# Hypex_PSU_v6.net
KiCad netlist of a schematic drawn in EAGLE
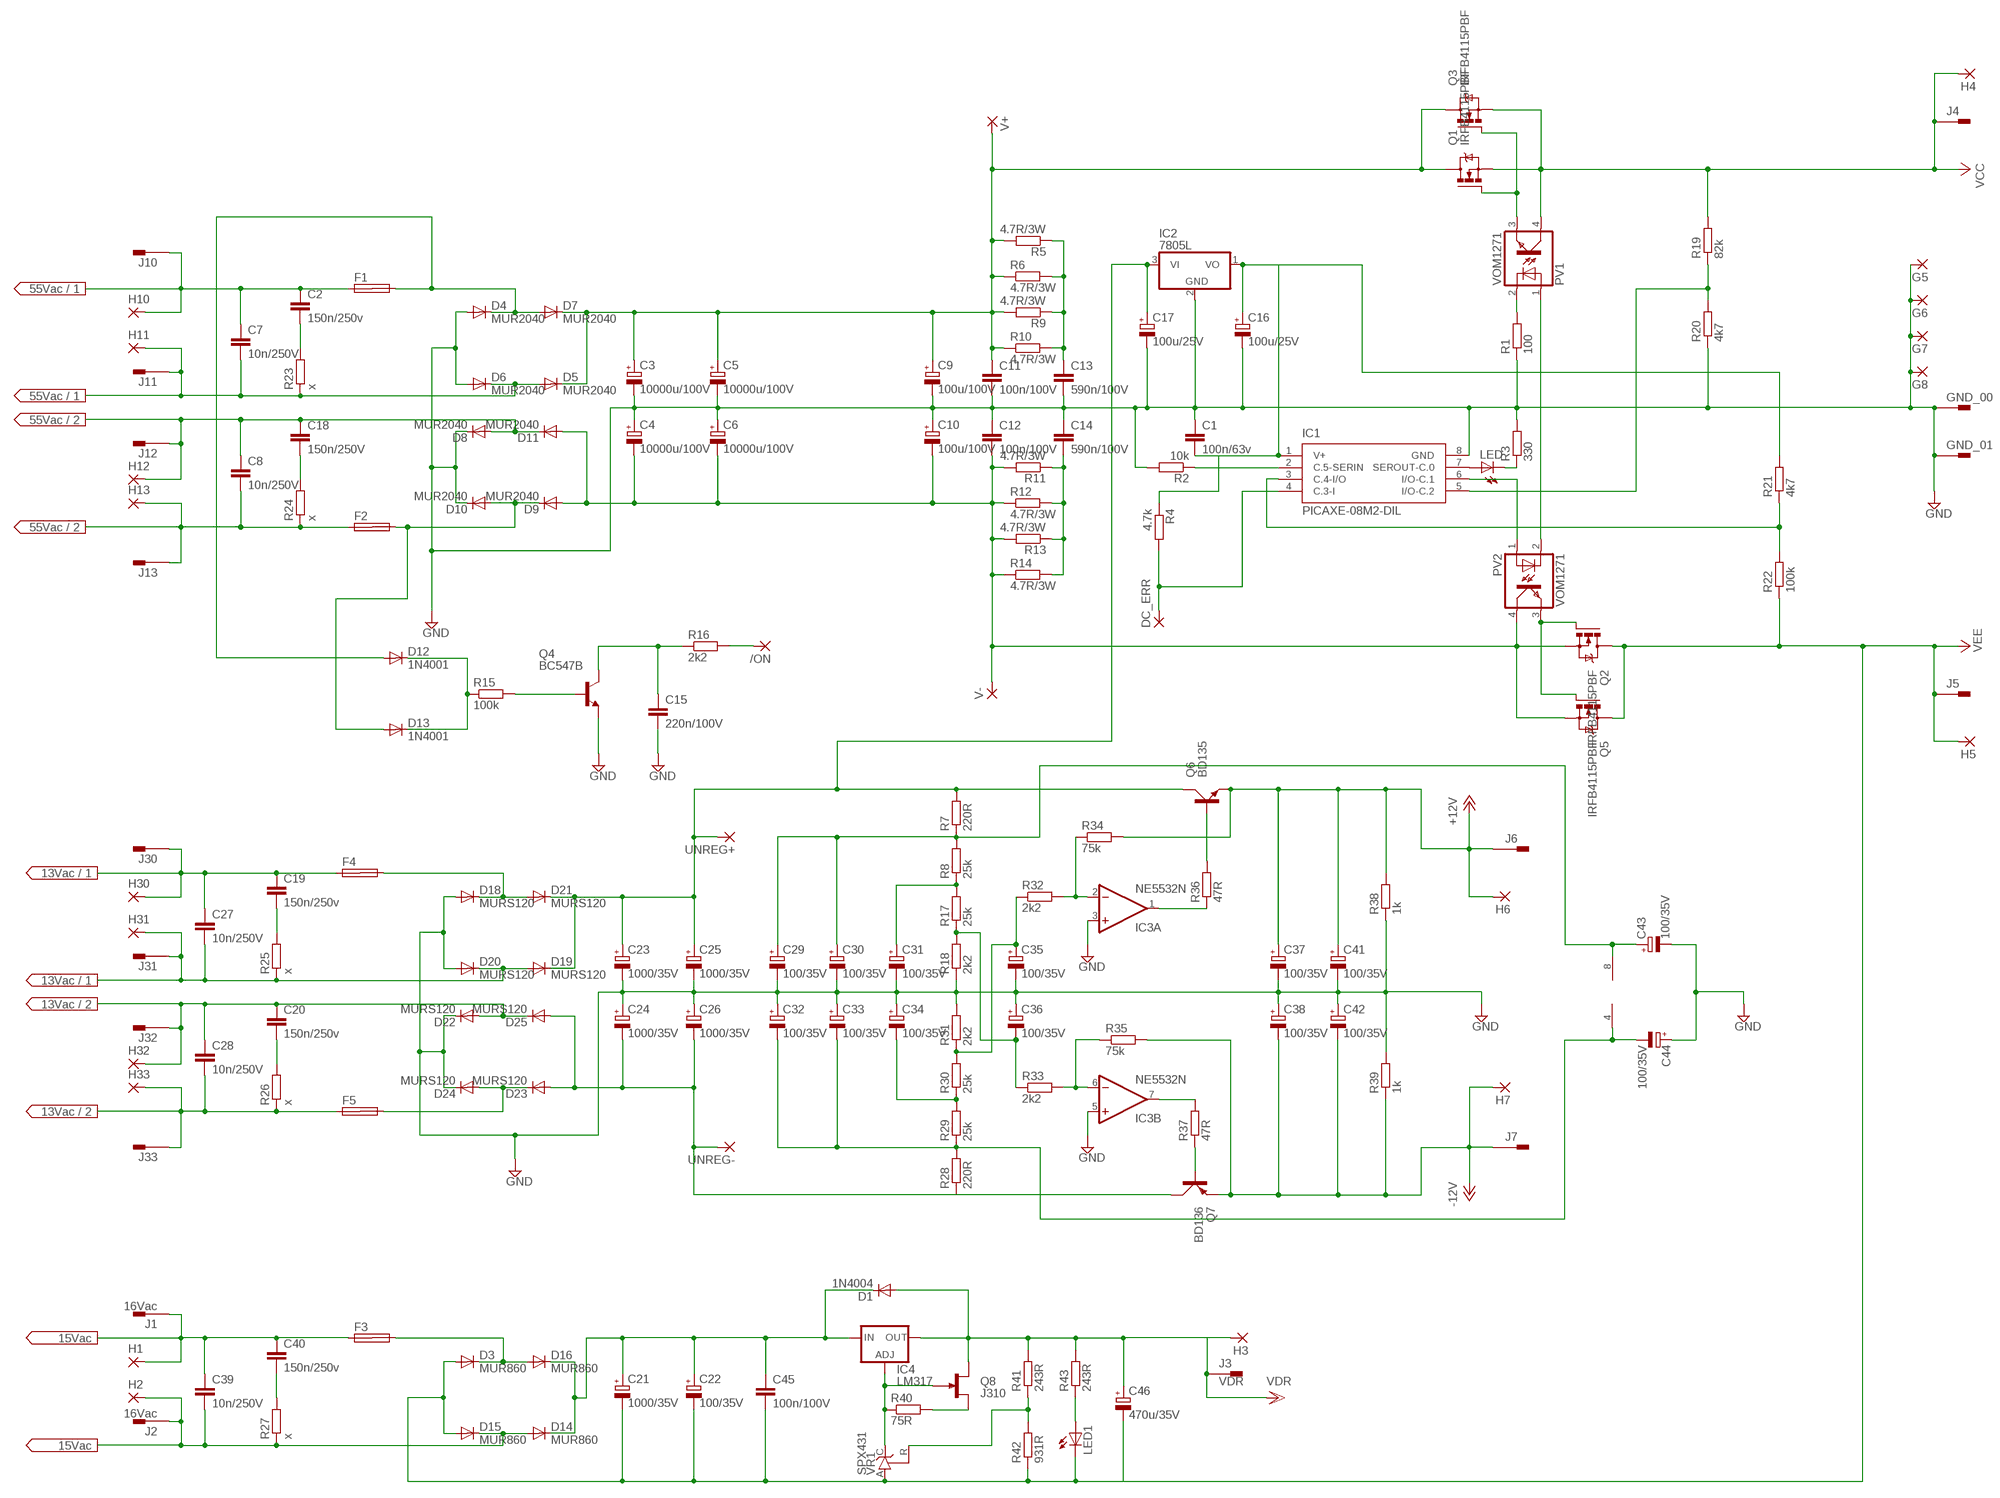
[diagram p0: schematic, sheet 1]

(export (version "E")
  (design (tool "Eeschema 10.0.6"))
  (components
    (comp (ref "/ON")
      (value "2,54/0,8")
      (footprint "eagle-import:2,54_0,8")
      (libsource (lib "eagle-import") (part "2,54/0,8"))
    )
    (comp (ref "C1")
      (value "100n/63v")
      (footprint "eagle-import:C050-025X075")
      (libsource (lib "eagle-import") (part "C-EU050-025X075"))
    )
    (comp (ref "C2")
      (value "150n/250v")
      (footprint "eagle-import:C102-064X133")
      (libsource (lib "eagle-import") (part "resistor_C-EU102-064X133"))
    )
    (comp (ref "C3")
      (value "10000u/100V")
      (footprint "eagle-import:EB35D")
      (libsource (lib "eagle-import") (part "CPOL-EUE10-35"))
    )
    (comp (ref "C4")
      (value "10000u/100V")
      (footprint "eagle-import:EB35D")
      (libsource (lib "eagle-import") (part "CPOL-EUE10-35"))
    )
    (comp (ref "C5")
      (value "10000u/100V")
      (footprint "eagle-import:EB35D")
      (libsource (lib "eagle-import") (part "CPOL-EUE10-35"))
    )
    (comp (ref "C6")
      (value "10000u/100V")
      (footprint "eagle-import:EB35D")
      (libsource (lib "eagle-import") (part "CPOL-EUE10-35"))
    )
    (comp (ref "C7")
      (value "10n/250V")
      (footprint "eagle-import:C102-064X133")
      (libsource (lib "eagle-import") (part "resistor_C-EU102-064X133"))
    )
    (comp (ref "C8")
      (value "10n/250V")
      (footprint "eagle-import:C102-064X133")
      (libsource (lib "eagle-import") (part "resistor_C-EU102-064X133"))
    )
    (comp (ref "C9")
      (value "100u/100V")
      (footprint "eagle-import:E5-10,5")
      (libsource (lib "eagle-import") (part "CPOL-EUE5-10.5"))
    )
    (comp (ref "C10")
      (value "100u/100V")
      (footprint "eagle-import:E5-10,5")
      (libsource (lib "eagle-import") (part "CPOL-EUE5-10.5"))
    )
    (comp (ref "C11")
      (value "100n/100V")
      (footprint "eagle-import:C102-064X133")
      (libsource (lib "eagle-import") (part "resistor_C-EU102-064X133"))
    )
    (comp (ref "C12")
      (value "100n/100V")
      (footprint "eagle-import:C102-064X133")
      (libsource (lib "eagle-import") (part "resistor_C-EU102-064X133"))
    )
    (comp (ref "C13")
      (value "590n/100V")
      (footprint "eagle-import:C102-064X133")
      (libsource (lib "eagle-import") (part "resistor_C-EU102-064X133"))
    )
    (comp (ref "C14")
      (value "590n/100V")
      (footprint "eagle-import:C102-064X133")
      (libsource (lib "eagle-import") (part "resistor_C-EU102-064X133"))
    )
    (comp (ref "C15")
      (value "220n/100V")
      (footprint "eagle-import:C102-064X133")
      (libsource (lib "eagle-import") (part "resistor_C-EU102-064X133"))
    )
    (comp (ref "C16")
      (value "100u/25V")
      (footprint "eagle-import:E3,5-8")
      (libsource (lib "eagle-import") (part "CPOL-EUE3.5-8"))
    )
    (comp (ref "C17")
      (value "100u/25V")
      (footprint "eagle-import:E3,5-8")
      (libsource (lib "eagle-import") (part "CPOL-EUE3.5-8"))
    )
    (comp (ref "C18")
      (value "150n/250V")
      (footprint "eagle-import:C102-064X133")
      (libsource (lib "eagle-import") (part "resistor_C-EU102-064X133"))
    )
    (comp (ref "C19")
      (value "150n/250v")
      (footprint "eagle-import:C102-064X133")
      (libsource (lib "eagle-import") (part "resistor_C-EU102-064X133"))
    )
    (comp (ref "C20")
      (value "150n/250v")
      (footprint "eagle-import:C102-064X133")
      (libsource (lib "eagle-import") (part "resistor_C-EU102-064X133"))
    )
    (comp (ref "C21")
      (value "1000/35V")
      (footprint "eagle-import:E5-13")
      (libsource (lib "eagle-import") (part "CPOL-EUE5-13"))
    )
    (comp (ref "C22")
      (value "100/35V")
      (footprint "eagle-import:E5-8,5")
      (libsource (lib "eagle-import") (part "CPOL-EUE5-8.5"))
    )
    (comp (ref "C23")
      (value "1000/35V")
      (footprint "eagle-import:E5-13")
      (libsource (lib "eagle-import") (part "CPOL-EUE5-13"))
    )
    (comp (ref "C24")
      (value "1000/35V")
      (footprint "eagle-import:E5-13")
      (libsource (lib "eagle-import") (part "CPOL-EUE5-13"))
    )
    (comp (ref "C25")
      (value "1000/35V")
      (footprint "eagle-import:E5-13")
      (libsource (lib "eagle-import") (part "CPOL-EUE5-13"))
    )
    (comp (ref "C26")
      (value "1000/35V")
      (footprint "eagle-import:E5-13")
      (libsource (lib "eagle-import") (part "CPOL-EUE5-13"))
    )
    (comp (ref "C27")
      (value "10n/250V")
      (footprint "eagle-import:C102-064X133")
      (libsource (lib "eagle-import") (part "resistor_C-EU102-064X133"))
    )
    (comp (ref "C28")
      (value "10n/250V")
      (footprint "eagle-import:C102-064X133")
      (libsource (lib "eagle-import") (part "resistor_C-EU102-064X133"))
    )
    (comp (ref "C29")
      (value "100/35V")
      (footprint "eagle-import:E5-8,5")
      (libsource (lib "eagle-import") (part "CPOL-EUE5-8.5"))
    )
    (comp (ref "C30")
      (value "100/35V")
      (footprint "eagle-import:E5-8,5")
      (libsource (lib "eagle-import") (part "CPOL-EUE5-8.5"))
    )
    (comp (ref "C31")
      (value "100/35V")
      (footprint "eagle-import:E5-8,5")
      (libsource (lib "eagle-import") (part "CPOL-EUE5-8.5"))
    )
    (comp (ref "C32")
      (value "100/35V")
      (footprint "eagle-import:E5-8,5")
      (libsource (lib "eagle-import") (part "CPOL-EUE5-8.5"))
    )
    (comp (ref "C33")
      (value "100/35V")
      (footprint "eagle-import:E5-8,5")
      (libsource (lib "eagle-import") (part "CPOL-EUE5-8.5"))
    )
    (comp (ref "C34")
      (value "100/35V")
      (footprint "eagle-import:E5-8,5")
      (libsource (lib "eagle-import") (part "CPOL-EUE5-8.5"))
    )
    (comp (ref "C35")
      (value "100/35V")
      (footprint "eagle-import:E5-8,5")
      (libsource (lib "eagle-import") (part "CPOL-EUE5-8.5"))
    )
    (comp (ref "C36")
      (value "100/35V")
      (footprint "eagle-import:E5-8,5")
      (libsource (lib "eagle-import") (part "CPOL-EUE5-8.5"))
    )
    (comp (ref "C37")
      (value "100/35V")
      (footprint "eagle-import:E5-8,5")
      (libsource (lib "eagle-import") (part "CPOL-EUE5-8.5"))
    )
    (comp (ref "C38")
      (value "100/35V")
      (footprint "eagle-import:E5-8,5")
      (libsource (lib "eagle-import") (part "CPOL-EUE5-8.5"))
    )
    (comp (ref "C39")
      (value "10n/250V")
      (footprint "eagle-import:C102-064X133")
      (libsource (lib "eagle-import") (part "resistor_C-EU102-064X133"))
    )
    (comp (ref "C40")
      (value "150n/250v")
      (footprint "eagle-import:C102-064X133")
      (libsource (lib "eagle-import") (part "resistor_C-EU102-064X133"))
    )
    (comp (ref "C41")
      (value "100/35V")
      (footprint "eagle-import:E5-8,5")
      (libsource (lib "eagle-import") (part "CPOL-EUE5-8.5"))
    )
    (comp (ref "C42")
      (value "100/35V")
      (footprint "eagle-import:E5-8,5")
      (libsource (lib "eagle-import") (part "CPOL-EUE5-8.5"))
    )
    (comp (ref "C43")
      (value "100/35V")
      (footprint "eagle-import:E5-8,5")
      (libsource (lib "eagle-import") (part "CPOL-EUE5-8.5"))
    )
    (comp (ref "C44")
      (value "100/35V")
      (footprint "eagle-import:E5-8,5")
      (libsource (lib "eagle-import") (part "CPOL-EUE5-8.5"))
    )
    (comp (ref "C45")
      (value "100n/100V")
      (footprint "eagle-import:C102-064X133")
      (libsource (lib "eagle-import") (part "resistor_C-EU102-064X133"))
    )
    (comp (ref "C46")
      (value "470u/35V")
      (footprint "eagle-import:E5-8,5")
      (libsource (lib "eagle-import") (part "CPOL-EUE5-8.5"))
    )
    (comp (ref "D1")
      (value "1N4004")
      (footprint "eagle-import:DO41-10")
      (libsource (lib "eagle-import") (part "1N4004"))
    )
    (comp (ref "D3")
      (value "MUR860")
      (footprint "eagle-import:TO220ACS")
      (libsource (lib "eagle-import") (part "MUR810"))
    )
    (comp (ref "D4")
      (value "MUR2040")
      (footprint "eagle-import:TO220ACS")
      (libsource (lib "eagle-import") (part "MUR810"))
    )
    (comp (ref "D5")
      (value "MUR2040")
      (footprint "eagle-import:TO220ACS")
      (libsource (lib "eagle-import") (part "MUR810"))
    )
    (comp (ref "D6")
      (value "MUR2040")
      (footprint "eagle-import:TO220ACS")
      (libsource (lib "eagle-import") (part "MUR810"))
    )
    (comp (ref "D7")
      (value "MUR2040")
      (footprint "eagle-import:TO220ACS")
      (libsource (lib "eagle-import") (part "MUR810"))
    )
    (comp (ref "D8")
      (value "MUR2040")
      (footprint "eagle-import:TO220ACS")
      (libsource (lib "eagle-import") (part "MUR810"))
    )
    (comp (ref "D9")
      (value "MUR2040")
      (footprint "eagle-import:TO220ACS")
      (libsource (lib "eagle-import") (part "MUR810"))
    )
    (comp (ref "D10")
      (value "MUR2040")
      (footprint "eagle-import:TO220ACS")
      (libsource (lib "eagle-import") (part "MUR810"))
    )
    (comp (ref "D11")
      (value "MUR2040")
      (footprint "eagle-import:TO220ACS")
      (libsource (lib "eagle-import") (part "MUR810"))
    )
    (comp (ref "D12")
      (value "1N4001")
      (footprint "eagle-import:DO41-10")
      (libsource (lib "eagle-import") (part "1N4004"))
    )
    (comp (ref "D13")
      (value "1N4001")
      (footprint "eagle-import:DO41-10")
      (libsource (lib "eagle-import") (part "1N4004"))
    )
    (comp (ref "D14")
      (value "MUR860")
      (footprint "eagle-import:TO220ACS")
      (libsource (lib "eagle-import") (part "MUR810"))
    )
    (comp (ref "D15")
      (value "MUR860")
      (footprint "eagle-import:TO220ACS")
      (libsource (lib "eagle-import") (part "MUR810"))
    )
    (comp (ref "D16")
      (value "MUR860")
      (footprint "eagle-import:TO220ACS")
      (libsource (lib "eagle-import") (part "MUR810"))
    )
    (comp (ref "D18")
      (value "MURS120")
      (footprint "eagle-import:TO220ACS")
      (libsource (lib "eagle-import") (part "MUR810"))
    )
    (comp (ref "D19")
      (value "MURS120")
      (footprint "eagle-import:TO220ACS")
      (libsource (lib "eagle-import") (part "MUR810"))
    )
    (comp (ref "D20")
      (value "MURS120")
      (footprint "eagle-import:TO220ACS")
      (libsource (lib "eagle-import") (part "MUR810"))
    )
    (comp (ref "D21")
      (value "MURS120")
      (footprint "eagle-import:TO220ACS")
      (libsource (lib "eagle-import") (part "MUR810"))
    )
    (comp (ref "D22")
      (value "MURS120")
      (footprint "eagle-import:TO220ACS")
      (libsource (lib "eagle-import") (part "MUR810"))
    )
    (comp (ref "D23")
      (value "MURS120")
      (footprint "eagle-import:TO220ACS")
      (libsource (lib "eagle-import") (part "MUR810"))
    )
    (comp (ref "D24")
      (value "MURS120")
      (footprint "eagle-import:TO220ACS")
      (libsource (lib "eagle-import") (part "MUR810"))
    )
    (comp (ref "D25")
      (value "MURS120")
      (footprint "eagle-import:TO220ACS")
      (libsource (lib "eagle-import") (part "MUR810"))
    )
    (comp (ref "DC_ERR")
      (value "2,54/0,8")
      (footprint "eagle-import:2,54_0,8")
      (libsource (lib "eagle-import") (part "2,54/0,8"))
    )
    (comp (ref "F1")
      (value "SHKOG")
      (footprint "eagle-import:SHKOG")
      (libsource (lib "eagle-import") (part "SHKOG"))
    )
    (comp (ref "F2")
      (value "SHKOG")
      (footprint "eagle-import:SHKOG")
      (libsource (lib "eagle-import") (part "SHKOG"))
    )
    (comp (ref "F3")
      (value "SHKOG")
      (footprint "eagle-import:SHKOG")
      (libsource (lib "eagle-import") (part "SHKOG"))
    )
    (comp (ref "F4")
      (value "SHKOG")
      (footprint "eagle-import:SHKOG")
      (libsource (lib "eagle-import") (part "SHKOG"))
    )
    (comp (ref "F5")
      (value "SHKOG")
      (footprint "eagle-import:SHKOG")
      (libsource (lib "eagle-import") (part "SHKOG"))
    )
    (comp (ref "G5")
      (value "3,17/1,3")
      (footprint "eagle-import:3,17_1,3")
      (libsource (lib "eagle-import") (part "3,17/1,3"))
    )
    (comp (ref "G6")
      (value "3,17/1,3")
      (footprint "eagle-import:3,17_1,3")
      (libsource (lib "eagle-import") (part "3,17/1,3"))
    )
    (comp (ref "G7")
      (value "3,17/1,3")
      (footprint "eagle-import:3,17_1,3")
      (libsource (lib "eagle-import") (part "3,17/1,3"))
    )
    (comp (ref "G8")
      (value "3,17/1,3")
      (footprint "eagle-import:3,17_1,3")
      (libsource (lib "eagle-import") (part "3,17/1,3"))
    )
    (comp (ref "GND_00")
      (value "PIN2F061.100")
      (footprint "eagle-import:F061.100")
      (libsource (lib "eagle-import") (part "PIN2F061.100"))
    )
    (comp (ref "GND_01")
      (value "PIN2F061.100")
      (footprint "eagle-import:F061.100")
      (libsource (lib "eagle-import") (part "PIN2F061.100"))
    )
    (comp (ref "H1")
      (value "3,81/1,4")
      (footprint "eagle-import:3,81_1,4")
      (libsource (lib "eagle-import") (part "3,81/1,4"))
    )
    (comp (ref "H2")
      (value "3,81/1,4")
      (footprint "eagle-import:3,81_1,4")
      (libsource (lib "eagle-import") (part "3,81/1,4"))
    )
    (comp (ref "H3")
      (value "3,81/1,4")
      (footprint "eagle-import:3,81_1,4")
      (libsource (lib "eagle-import") (part "3,81/1,4"))
    )
    (comp (ref "H4")
      (value "3,17/1,3")
      (footprint "eagle-import:3,17_1,3")
      (libsource (lib "eagle-import") (part "3,17/1,3"))
    )
    (comp (ref "H5")
      (value "3,17/1,3")
      (footprint "eagle-import:3,17_1,3")
      (libsource (lib "eagle-import") (part "3,17/1,3"))
    )
    (comp (ref "H6")
      (value "3,81/1,4")
      (footprint "eagle-import:3,81_1,4")
      (libsource (lib "eagle-import") (part "3,81/1,4"))
    )
    (comp (ref "H7")
      (value "3,81/1,4")
      (footprint "eagle-import:3,81_1,4")
      (libsource (lib "eagle-import") (part "3,81/1,4"))
    )
    (comp (ref "H10")
      (value "3,81/1,4")
      (footprint "eagle-import:3,81_1,4")
      (libsource (lib "eagle-import") (part "3,81/1,4"))
    )
    (comp (ref "H11")
      (value "3,81/1,4")
      (footprint "eagle-import:3,81_1,4")
      (libsource (lib "eagle-import") (part "3,81/1,4"))
    )
    (comp (ref "H12")
      (value "3,81/1,4")
      (footprint "eagle-import:3,81_1,4")
      (libsource (lib "eagle-import") (part "3,81/1,4"))
    )
    (comp (ref "H13")
      (value "3,81/1,4")
      (footprint "eagle-import:3,81_1,4")
      (libsource (lib "eagle-import") (part "3,81/1,4"))
    )
    (comp (ref "H30")
      (value "3,81/1,4")
      (footprint "eagle-import:3,81_1,4")
      (libsource (lib "eagle-import") (part "3,81/1,4"))
    )
    (comp (ref "H31")
      (value "3,81/1,4")
      (footprint "eagle-import:3,81_1,4")
      (libsource (lib "eagle-import") (part "3,81/1,4"))
    )
    (comp (ref "H32")
      (value "3,81/1,4")
      (footprint "eagle-import:3,81_1,4")
      (libsource (lib "eagle-import") (part "3,81/1,4"))
    )
    (comp (ref "H33")
      (value "3,81/1,4")
      (footprint "eagle-import:3,81_1,4")
      (libsource (lib "eagle-import") (part "3,81/1,4"))
    )
    (comp (ref "IC1")
      (value "PICAXE-08M2-DIL")
      (footprint "eagle-import:DIL8")
      (libsource (lib "eagle-import") (part "PICAXE-08M2-DIL"))
    )
    (comp (ref "IC2")
      (value "7805L")
      (footprint "eagle-import:TO92")
      (libsource (lib "eagle-import") (part "78L05"))
    )
    (comp (ref "IC3")
      (value "NE5532N")
      (footprint "eagle-import:DIL08")
      (libsource (lib "eagle-import") (part "NE5532N"))
    )
    (comp (ref "IC4")
      (value "LM317")
      (footprint "eagle-import:317TS")
      (libsource (lib "eagle-import") (part "LM317TS"))
    )
    (comp (ref "J1")
      (value "16Vac")
      (footprint "eagle-import:F061.100")
      (libsource (lib "eagle-import") (part "PIN2F061.100"))
    )
    (comp (ref "J2")
      (value "16Vac")
      (footprint "eagle-import:F061.100")
      (libsource (lib "eagle-import") (part "PIN2F061.100"))
    )
    (comp (ref "J3")
      (value "VDR")
      (footprint "eagle-import:F061.100")
      (libsource (lib "eagle-import") (part "PIN2F061.100"))
    )
    (comp (ref "J4")
      (value "PIN2F061.100")
      (footprint "eagle-import:F061.100")
      (libsource (lib "eagle-import") (part "PIN2F061.100"))
    )
    (comp (ref "J5")
      (value "PIN2F061.100")
      (footprint "eagle-import:F061.100")
      (libsource (lib "eagle-import") (part "PIN2F061.100"))
    )
    (comp (ref "J6")
      (value "PIN2F061.100")
      (footprint "eagle-import:F061.100")
      (libsource (lib "eagle-import") (part "PIN2F061.100"))
    )
    (comp (ref "J7")
      (value "PIN2F061.100")
      (footprint "eagle-import:F061.100")
      (libsource (lib "eagle-import") (part "PIN2F061.100"))
    )
    (comp (ref "J10")
      (value "PIN2F061.100")
      (footprint "eagle-import:F061.100")
      (libsource (lib "eagle-import") (part "PIN2F061.100"))
    )
    (comp (ref "J11")
      (value "PIN2F061.100")
      (footprint "eagle-import:F061.100")
      (libsource (lib "eagle-import") (part "PIN2F061.100"))
    )
    (comp (ref "J12")
      (value "PIN2F061.100")
      (footprint "eagle-import:F061.100")
      (libsource (lib "eagle-import") (part "PIN2F061.100"))
    )
    (comp (ref "J13")
      (value "PIN2F061.100")
      (footprint "eagle-import:F061.100")
      (libsource (lib "eagle-import") (part "PIN2F061.100"))
    )
    (comp (ref "J30")
      (value "PIN2F061.100")
      (footprint "eagle-import:F061.100")
      (libsource (lib "eagle-import") (part "PIN2F061.100"))
    )
    (comp (ref "J31")
      (value "PIN2F061.100")
      (footprint "eagle-import:F061.100")
      (libsource (lib "eagle-import") (part "PIN2F061.100"))
    )
    (comp (ref "J32")
      (value "PIN2F061.100")
      (footprint "eagle-import:F061.100")
      (libsource (lib "eagle-import") (part "PIN2F061.100"))
    )
    (comp (ref "J33")
      (value "PIN2F061.100")
      (footprint "eagle-import:F061.100")
      (libsource (lib "eagle-import") (part "PIN2F061.100"))
    )
    (comp (ref "LED")
      (value "LED3MM")
      (footprint "eagle-import:LED3MM")
      (libsource (lib "eagle-import") (part "LED3MM"))
    )
    (comp (ref "LED1")
      (value "LED3MM")
      (footprint "eagle-import:LED3MM")
      (libsource (lib "eagle-import") (part "LED3MM"))
    )
    (comp (ref "PV1")
      (value "VOM1271")
      (footprint "eagle-import:SMD4")
      (libsource (lib "eagle-import") (part "LTV816S"))
    )
    (comp (ref "PV2")
      (value "VOM1271")
      (footprint "eagle-import:SMD4")
      (libsource (lib "eagle-import") (part "LTV816S"))
    )
    (comp (ref "Q1")
      (value "IRFB4115PBF")
      (footprint "eagle-import:TO220BV")
      (libsource (lib "eagle-import") (part "IRF540"))
    )
    (comp (ref "Q2")
      (value "IRFB4115PBF")
      (footprint "eagle-import:TO220BV")
      (libsource (lib "eagle-import") (part "IRF540"))
    )
    (comp (ref "Q3")
      (value "IRFB4115PBF")
      (footprint "eagle-import:TO220BV")
      (libsource (lib "eagle-import") (part "IRF540"))
    )
    (comp (ref "Q4")
      (value "BC547B")
      (footprint "eagle-import:TO92")
      (libsource (lib "eagle-import") (part "BC547B"))
    )
    (comp (ref "Q5")
      (value "IRFB4115PBF")
      (footprint "eagle-import:TO220BV")
      (libsource (lib "eagle-import") (part "IRF540"))
    )
    (comp (ref "Q6")
      (value "BD135")
      (footprint "eagle-import:TO126AV")
      (libsource (lib "eagle-import") (part "BD139"))
    )
    (comp (ref "Q7")
      (value "BD136")
      (footprint "eagle-import:TO126AV")
      (libsource (lib "eagle-import") (part "BD140"))
    )
    (comp (ref "Q8")
      (value "J310")
      (footprint "eagle-import:TO92R")
      (libsource (lib "eagle-import") (part "J310"))
    )
    (comp (ref "R1")
      (value "100")
      (footprint "eagle-import:0207_10")
      (libsource (lib "eagle-import") (part "R-EU_0207/10"))
    )
    (comp (ref "R2")
      (value "10k")
      (footprint "eagle-import:0207_10")
      (libsource (lib "eagle-import") (part "R-EU_0207/10"))
    )
    (comp (ref "R3")
      (value "330")
      (footprint "eagle-import:0207_10")
      (libsource (lib "eagle-import") (part "R-EU_0207/10"))
    )
    (comp (ref "R4")
      (value "4.7k")
      (footprint "eagle-import:0207_10")
      (libsource (lib "eagle-import") (part "R-EU_0207/10"))
    )
    (comp (ref "R5")
      (value "4.7R/3W")
      (footprint "eagle-import:0617V")
      (libsource (lib "eagle-import") (part "R-EU_0617/5V"))
    )
    (comp (ref "R6")
      (value "4.7R/3W")
      (footprint "eagle-import:0617V")
      (libsource (lib "eagle-import") (part "R-EU_0617/5V"))
    )
    (comp (ref "R7")
      (value "220R")
      (footprint "eagle-import:0207_10")
      (libsource (lib "eagle-import") (part "R-EU_0207/10"))
    )
    (comp (ref "R8")
      (value "25k")
      (footprint "eagle-import:0207_10")
      (libsource (lib "eagle-import") (part "R-EU_0207/10"))
    )
    (comp (ref "R9")
      (value "4.7R/3W")
      (footprint "eagle-import:0617V")
      (libsource (lib "eagle-import") (part "R-EU_0617/5V"))
    )
    (comp (ref "R10")
      (value "4.7R/3W")
      (footprint "eagle-import:0617V")
      (libsource (lib "eagle-import") (part "R-EU_0617/5V"))
    )
    (comp (ref "R11")
      (value "4.7R/3W")
      (footprint "eagle-import:0617V")
      (libsource (lib "eagle-import") (part "R-EU_0617/5V"))
    )
    (comp (ref "R12")
      (value "4.7R/3W")
      (footprint "eagle-import:0617V")
      (libsource (lib "eagle-import") (part "R-EU_0617/5V"))
    )
    (comp (ref "R13")
      (value "4.7R/3W")
      (footprint "eagle-import:0617V")
      (libsource (lib "eagle-import") (part "R-EU_0617/5V"))
    )
    (comp (ref "R14")
      (value "4.7R/3W")
      (footprint "eagle-import:0617V")
      (libsource (lib "eagle-import") (part "R-EU_0617/5V"))
    )
    (comp (ref "R15")
      (value "100k")
      (footprint "eagle-import:0207_10")
      (libsource (lib "eagle-import") (part "R-EU_0207/10"))
    )
    (comp (ref "R16")
      (value "2k2")
      (footprint "eagle-import:0207_10")
      (libsource (lib "eagle-import") (part "R-EU_0207/10"))
    )
    (comp (ref "R17")
      (value "25k")
      (footprint "eagle-import:0207_10")
      (libsource (lib "eagle-import") (part "R-EU_0207/10"))
    )
    (comp (ref "R18")
      (value "2k2")
      (footprint "eagle-import:0207_10")
      (libsource (lib "eagle-import") (part "R-EU_0207/10"))
    )
    (comp (ref "R19")
      (value "82k")
      (footprint "eagle-import:0207_10")
      (libsource (lib "eagle-import") (part "R-EU_0207/10"))
    )
    (comp (ref "R20")
      (value "4k7")
      (footprint "eagle-import:0207_10")
      (libsource (lib "eagle-import") (part "R-EU_0207/10"))
    )
    (comp (ref "R21")
      (value "4k7")
      (footprint "eagle-import:0207_10")
      (libsource (lib "eagle-import") (part "R-EU_0207/10"))
    )
    (comp (ref "R22")
      (value "100k")
      (footprint "eagle-import:0207_10")
      (libsource (lib "eagle-import") (part "R-EU_0207/10"))
    )
    (comp (ref "R23")
      (value "x")
      (footprint "eagle-import:0207_7")
      (libsource (lib "eagle-import") (part "R-EU_0207/7"))
    )
    (comp (ref "R24")
      (value "x")
      (footprint "eagle-import:0207_7")
      (libsource (lib "eagle-import") (part "R-EU_0207/7"))
    )
    (comp (ref "R25")
      (value "x")
      (footprint "eagle-import:0207_10")
      (libsource (lib "eagle-import") (part "R-EU_0207/10"))
    )
    (comp (ref "R26")
      (value "x")
      (footprint "eagle-import:0207_10")
      (libsource (lib "eagle-import") (part "R-EU_0207/10"))
    )
    (comp (ref "R27")
      (value "x")
      (footprint "eagle-import:0207_10")
      (libsource (lib "eagle-import") (part "R-EU_0207/10"))
    )
    (comp (ref "R28")
      (value "220R")
      (footprint "eagle-import:0207_10")
      (libsource (lib "eagle-import") (part "R-EU_0207/10"))
    )
    (comp (ref "R29")
      (value "25k")
      (footprint "eagle-import:0207_10")
      (libsource (lib "eagle-import") (part "R-EU_0207/10"))
    )
    (comp (ref "R30")
      (value "25k")
      (footprint "eagle-import:0207_10")
      (libsource (lib "eagle-import") (part "R-EU_0207/10"))
    )
    (comp (ref "R31")
      (value "2k2")
      (footprint "eagle-import:0207_10")
      (libsource (lib "eagle-import") (part "R-EU_0207/10"))
    )
    (comp (ref "R32")
      (value "2k2")
      (footprint "eagle-import:0207_10")
      (libsource (lib "eagle-import") (part "R-EU_0207/10"))
    )
    (comp (ref "R33")
      (value "2k2")
      (footprint "eagle-import:0207_10")
      (libsource (lib "eagle-import") (part "R-EU_0207/10"))
    )
    (comp (ref "R34")
      (value "75k")
      (footprint "eagle-import:0207_10")
      (libsource (lib "eagle-import") (part "R-EU_0207/10"))
    )
    (comp (ref "R35")
      (value "75k")
      (footprint "eagle-import:0207_10")
      (libsource (lib "eagle-import") (part "R-EU_0207/10"))
    )
    (comp (ref "R36")
      (value "47R")
      (footprint "eagle-import:0207_10")
      (libsource (lib "eagle-import") (part "R-EU_0207/10"))
    )
    (comp (ref "R37")
      (value "47R")
      (footprint "eagle-import:0207_10")
      (libsource (lib "eagle-import") (part "R-EU_0207/10"))
    )
    (comp (ref "R38")
      (value "1k")
      (footprint "eagle-import:0207_10")
      (libsource (lib "eagle-import") (part "R-EU_0207/10"))
    )
    (comp (ref "R39")
      (value "1k")
      (footprint "eagle-import:0207_10")
      (libsource (lib "eagle-import") (part "R-EU_0207/10"))
    )
    (comp (ref "R40")
      (value "75R")
      (footprint "eagle-import:0207_10")
      (libsource (lib "eagle-import") (part "R-EU_0207/10"))
    )
    (comp (ref "R41")
      (value "243R")
      (footprint "eagle-import:0207_10")
      (libsource (lib "eagle-import") (part "R-EU_0207/10"))
    )
    (comp (ref "R42")
      (value "931R")
      (footprint "eagle-import:0207_10")
      (libsource (lib "eagle-import") (part "R-EU_0207/10"))
    )
    (comp (ref "R43")
      (value "243R")
      (footprint "eagle-import:0207_10")
      (libsource (lib "eagle-import") (part "R-EU_0207/10"))
    )
    (comp (ref "UNREG+")
      (value "3,81/1,4")
      (footprint "eagle-import:3,81_1,4")
      (libsource (lib "eagle-import") (part "3,81/1,4"))
    )
    (comp (ref "UNREG-")
      (value "3,81/1,4")
      (footprint "eagle-import:3,81_1,4")
      (libsource (lib "eagle-import") (part "3,81/1,4"))
    )
    (comp (ref "V+")
      (value "3,81/1,4")
      (footprint "eagle-import:3,81_1,4")
      (libsource (lib "eagle-import") (part "3,81/1,4"))
    )
    (comp (ref "V-")
      (value "3,81/1,4")
      (footprint "eagle-import:3,81_1,4")
      (libsource (lib "eagle-import") (part "3,81/1,4"))
    )
    (comp (ref "VR1")
      (value "SPX431")
      (footprint "eagle-import:TO92-CLP")
      (libsource (lib "eagle-import") (part "TL431CLP"))
    )
  )
  (nets
    (net (code "1") (name "+12V") (class "Default")
      (node (ref "C37") (pin "+") (pinfunction "+_+") (pintype "passive"))
      (node (ref "C41") (pin "+") (pinfunction "+_+") (pintype "passive"))
      (node (ref "H6") (pin "1") (pinfunction "P_1") (pintype "passive"))
      (node (ref "J6") (pin "A1") (pinfunction "1_A1") (pintype "passive"))
      (node (ref "J6") (pin "A2") (pinfunction "1_A2") (pintype "passive"))
      (node (ref "Q6") (pin "E") (pinfunction "E_E") (pintype "passive"))
      (node (ref "R34") (pin "2") (pinfunction "2_2") (pintype "passive"))
      (node (ref "R38") (pin "2") (pinfunction "2_2") (pintype "passive"))
    )
    (net (code "2") (name "-12V") (class "Default")
      (node (ref "C38") (pin "-") (pinfunction "-_-") (pintype "passive"))
      (node (ref "C42") (pin "-") (pinfunction "-_-") (pintype "passive"))
      (node (ref "H7") (pin "1") (pinfunction "P_1") (pintype "passive"))
      (node (ref "J7") (pin "A1") (pinfunction "1_A1") (pintype "passive"))
      (node (ref "J7") (pin "A2") (pinfunction "1_A2") (pintype "passive"))
      (node (ref "Q7") (pin "E") (pinfunction "E_E") (pintype "passive"))
      (node (ref "R35") (pin "2") (pinfunction "2_2") (pintype "passive"))
      (node (ref "R39") (pin "1") (pinfunction "1_1") (pintype "passive"))
    )
    (net (code "3") (name "GND") (class "Default")
      (node (ref "C1") (pin "1") (pinfunction "1_1") (pintype "passive"))
      (node (ref "C10") (pin "+") (pinfunction "+_+") (pintype "passive"))
      (node (ref "C11") (pin "2") (pinfunction "2_2") (pintype "passive"))
      (node (ref "C12") (pin "1") (pinfunction "1_1") (pintype "passive"))
      (node (ref "C13") (pin "2") (pinfunction "2_2") (pintype "passive"))
      (node (ref "C14") (pin "1") (pinfunction "1_1") (pintype "passive"))
      (node (ref "C15") (pin "2") (pinfunction "2_2") (pintype "passive"))
      (node (ref "C16") (pin "-") (pinfunction "-_-") (pintype "passive"))
      (node (ref "C17") (pin "-") (pinfunction "-_-") (pintype "passive"))
      (node (ref "C23") (pin "-") (pinfunction "-_-") (pintype "passive"))
      (node (ref "C24") (pin "+") (pinfunction "+_+") (pintype "passive"))
      (node (ref "C25") (pin "-") (pinfunction "-_-") (pintype "passive"))
      (node (ref "C26") (pin "+") (pinfunction "+_+") (pintype "passive"))
      (node (ref "C29") (pin "-") (pinfunction "-_-") (pintype "passive"))
      (node (ref "C3") (pin "-") (pinfunction "-_-") (pintype "passive"))
      (node (ref "C30") (pin "-") (pinfunction "-_-") (pintype "passive"))
      (node (ref "C31") (pin "-") (pinfunction "-_-") (pintype "passive"))
      (node (ref "C32") (pin "+") (pinfunction "+_+") (pintype "passive"))
      (node (ref "C33") (pin "+") (pinfunction "+_+") (pintype "passive"))
      (node (ref "C34") (pin "+") (pinfunction "+_+") (pintype "passive"))
      (node (ref "C35") (pin "-") (pinfunction "-_-") (pintype "passive"))
      (node (ref "C36") (pin "+") (pinfunction "+_+") (pintype "passive"))
      (node (ref "C37") (pin "-") (pinfunction "-_-") (pintype "passive"))
      (node (ref "C38") (pin "+") (pinfunction "+_+") (pintype "passive"))
      (node (ref "C4") (pin "+") (pinfunction "+_+") (pintype "passive"))
      (node (ref "C41") (pin "-") (pinfunction "-_-") (pintype "passive"))
      (node (ref "C42") (pin "+") (pinfunction "+_+") (pintype "passive"))
      (node (ref "C43") (pin "-") (pinfunction "-_-") (pintype "passive"))
      (node (ref "C44") (pin "+") (pinfunction "+_+") (pintype "passive"))
      (node (ref "C5") (pin "-") (pinfunction "-_-") (pintype "passive"))
      (node (ref "C6") (pin "+") (pinfunction "+_+") (pintype "passive"))
      (node (ref "C9") (pin "-") (pinfunction "-_-") (pintype "passive"))
      (node (ref "D10") (pin "C") (pinfunction "C_C") (pintype "passive"))
      (node (ref "D18") (pin "A") (pinfunction "A_A") (pintype "passive"))
      (node (ref "D20") (pin "A") (pinfunction "A_A") (pintype "passive"))
      (node (ref "D22") (pin "C") (pinfunction "C_C") (pintype "passive"))
      (node (ref "D24") (pin "C") (pinfunction "C_C") (pintype "passive"))
      (node (ref "D4") (pin "A") (pinfunction "A_A") (pintype "passive"))
      (node (ref "D6") (pin "A") (pinfunction "A_A") (pintype "passive"))
      (node (ref "D8") (pin "C") (pinfunction "C_C") (pintype "passive"))
      (node (ref "G5") (pin "1") (pinfunction "P_1") (pintype "passive"))
      (node (ref "G6") (pin "1") (pinfunction "P_1") (pintype "passive"))
      (node (ref "G7") (pin "1") (pinfunction "P_1") (pintype "passive"))
      (node (ref "G8") (pin "1") (pinfunction "P_1") (pintype "passive"))
      (node (ref "GND_00") (pin "A1") (pinfunction "1_A1") (pintype "passive"))
      (node (ref "GND_00") (pin "A2") (pinfunction "1_A2") (pintype "passive"))
      (node (ref "GND_01") (pin "A1") (pinfunction "1_A1") (pintype "passive"))
      (node (ref "GND_01") (pin "A2") (pinfunction "1_A2") (pintype "passive"))
      (node (ref "IC1") (pin "8") (pinfunction "GND_8") (pintype "power_in"))
      (node (ref "IC2") (pin "2") (pinfunction "GND_2") (pintype "passive"))
      (node (ref "IC3") (pin "3") (pinfunction "+IN_3") (pintype "input"))
      (node (ref "IC3") (pin "5") (pinfunction "+IN_5") (pintype "input"))
      (node (ref "Q4") (pin "1") (pinfunction "E_1") (pintype "passive"))
      (node (ref "R1") (pin "1") (pinfunction "1_1") (pintype "passive"))
      (node (ref "R18") (pin "1") (pinfunction "1_1") (pintype "passive"))
      (node (ref "R2") (pin "2") (pinfunction "2_2") (pintype "passive"))
      (node (ref "R20") (pin "1") (pinfunction "1_1") (pintype "passive"))
      (node (ref "R3") (pin "2") (pinfunction "2_2") (pintype "passive"))
      (node (ref "R31") (pin "2") (pinfunction "2_2") (pintype "passive"))
      (node (ref "R38") (pin "1") (pinfunction "1_1") (pintype "passive"))
      (node (ref "R39") (pin "2") (pinfunction "2_2") (pintype "passive"))
    )
    (net (code "4") (name "Net-(/ON-P)") (class "Default")
      (node (ref "/ON") (pin "1") (pinfunction "P_1") (pintype "passive"))
      (node (ref "R16") (pin "2") (pinfunction "2_2") (pintype "passive"))
    )
    (net (code "5") (name "Net-(C2-Pad2)") (class "Default")
      (node (ref "C2") (pin "2") (pinfunction "2_2") (pintype "passive"))
      (node (ref "R23") (pin "2") (pinfunction "2_2") (pintype "passive"))
    )
    (net (code "6") (name "Net-(C13-Pad1)") (class "Default")
      (node (ref "C13") (pin "1") (pinfunction "1_1") (pintype "passive"))
      (node (ref "R10") (pin "2") (pinfunction "2_2") (pintype "passive"))
      (node (ref "R5") (pin "1") (pinfunction "1_1") (pintype "passive"))
      (node (ref "R6") (pin "2") (pinfunction "2_2") (pintype "passive"))
      (node (ref "R9") (pin "1") (pinfunction "1_1") (pintype "passive"))
    )
    (net (code "7") (name "Net-(C14-Pad2)") (class "Default")
      (node (ref "C14") (pin "2") (pinfunction "2_2") (pintype "passive"))
      (node (ref "R11") (pin "1") (pinfunction "1_1") (pintype "passive"))
      (node (ref "R12") (pin "2") (pinfunction "2_2") (pintype "passive"))
      (node (ref "R13") (pin "1") (pinfunction "1_1") (pintype "passive"))
      (node (ref "R14") (pin "2") (pinfunction "2_2") (pintype "passive"))
    )
    (net (code "8") (name "Net-(C18-Pad2)") (class "Default")
      (node (ref "C18") (pin "2") (pinfunction "2_2") (pintype "passive"))
      (node (ref "R24") (pin "2") (pinfunction "2_2") (pintype "passive"))
    )
    (net (code "9") (name "Net-(C19-Pad2)") (class "Default")
      (node (ref "C19") (pin "2") (pinfunction "2_2") (pintype "passive"))
      (node (ref "R25") (pin "2") (pinfunction "2_2") (pintype "passive"))
    )
    (net (code "10") (name "Net-(C20-Pad2)") (class "Default")
      (node (ref "C20") (pin "2") (pinfunction "2_2") (pintype "passive"))
      (node (ref "R26") (pin "2") (pinfunction "2_2") (pintype "passive"))
    )
    (net (code "11") (name "Net-(C31-Pad+)") (class "Default")
      (node (ref "C31") (pin "+") (pinfunction "+_+") (pintype "passive"))
      (node (ref "R17") (pin "2") (pinfunction "2_2") (pintype "passive"))
      (node (ref "R8") (pin "1") (pinfunction "1_1") (pintype "passive"))
    )
    (net (code "12") (name "Net-(C34-Pad-)") (class "Default")
      (node (ref "C34") (pin "-") (pinfunction "-_-") (pintype "passive"))
      (node (ref "R29") (pin "2") (pinfunction "2_2") (pintype "passive"))
      (node (ref "R30") (pin "1") (pinfunction "1_1") (pintype "passive"))
    )
    (net (code "13") (name "Net-(C35-Pad+)") (class "Default")
      (node (ref "C35") (pin "+") (pinfunction "+_+") (pintype "passive"))
      (node (ref "R30") (pin "2") (pinfunction "2_2") (pintype "passive"))
      (node (ref "R31") (pin "1") (pinfunction "1_1") (pintype "passive"))
      (node (ref "R32") (pin "1") (pinfunction "1_1") (pintype "passive"))
    )
    (net (code "14") (name "Net-(C36-Pad-)") (class "Default")
      (node (ref "C36") (pin "-") (pinfunction "-_-") (pintype "passive"))
      (node (ref "R17") (pin "1") (pinfunction "1_1") (pintype "passive"))
      (node (ref "R18") (pin "2") (pinfunction "2_2") (pintype "passive"))
      (node (ref "R33") (pin "1") (pinfunction "1_1") (pintype "passive"))
    )
    (net (code "15") (name "Net-(C40-Pad2)") (class "Default")
      (node (ref "C40") (pin "2") (pinfunction "2_2") (pintype "passive"))
      (node (ref "R27") (pin "2") (pinfunction "2_2") (pintype "passive"))
    )
    (net (code "16") (name "Net-(D10-PadA)") (class "Default")
      (node (ref "D10") (pin "A") (pinfunction "A_A") (pintype "passive"))
      (node (ref "D13") (pin "A") (pinfunction "A_A") (pintype "passive"))
      (node (ref "D9") (pin "C") (pinfunction "C_C") (pintype "passive"))
      (node (ref "F2") (pin "2A") (pinfunction "2A_2A") (pintype "passive"))
    )
    (net (code "17") (name "Net-(D12-PadA)") (class "Default")
      (node (ref "D12") (pin "A") (pinfunction "A_A") (pintype "passive"))
      (node (ref "D4") (pin "C") (pinfunction "C_C") (pintype "passive"))
      (node (ref "D7") (pin "A") (pinfunction "A_A") (pintype "passive"))
      (node (ref "F1") (pin "2A") (pinfunction "2A_2A") (pintype "passive"))
    )
    (net (code "18") (name "Net-(D12-PadC)") (class "Default")
      (node (ref "D12") (pin "C") (pinfunction "C_C") (pintype "passive"))
      (node (ref "D13") (pin "C") (pinfunction "C_C") (pintype "passive"))
      (node (ref "R15") (pin "1") (pinfunction "1_1") (pintype "passive"))
    )
    (net (code "19") (name "Net-(D16-PadA)") (class "Default")
      (node (ref "D16") (pin "A") (pinfunction "A_A") (pintype "passive"))
      (node (ref "D3") (pin "C") (pinfunction "C_C") (pintype "passive"))
      (node (ref "F3") (pin "2A") (pinfunction "2A_2A") (pintype "passive"))
    )
    (net (code "20") (name "Net-(D18-PadC)") (class "Default")
      (node (ref "D18") (pin "C") (pinfunction "C_C") (pintype "passive"))
      (node (ref "D21") (pin "A") (pinfunction "A_A") (pintype "passive"))
      (node (ref "F4") (pin "2A") (pinfunction "2A_2A") (pintype "passive"))
    )
    (net (code "21") (name "Net-(D23-PadC)") (class "Default")
      (node (ref "D23") (pin "C") (pinfunction "C_C") (pintype "passive"))
      (node (ref "D24") (pin "A") (pinfunction "A_A") (pintype "passive"))
      (node (ref "F5") (pin "2A") (pinfunction "2A_2A") (pintype "passive"))
    )
    (net (code "22") (name "Net-(DC_ERR-P)") (class "Default")
      (node (ref "DC_ERR") (pin "1") (pinfunction "P_1") (pintype "passive"))
      (node (ref "IC1") (pin "4") (pinfunction "C.3-I_4") (pintype "input"))
      (node (ref "R4") (pin "2") (pinfunction "2_2") (pintype "passive"))
    )
    (net (code "23") (name "Net-(H1-P)") (class "Default")
      (node (ref "C39") (pin "1") (pinfunction "1_1") (pintype "passive"))
      (node (ref "C40") (pin "1") (pinfunction "1_1") (pintype "passive"))
      (node (ref "F3") (pin "1A") (pinfunction "1A_1A") (pintype "passive"))
      (node (ref "H1") (pin "1") (pinfunction "P_1") (pintype "passive"))
      (node (ref "J1") (pin "A1") (pinfunction "1_A1") (pintype "passive"))
      (node (ref "J1") (pin "A2") (pinfunction "1_A2") (pintype "passive"))
    )
    (net (code "24") (name "Net-(H2-P)") (class "Default")
      (node (ref "C39") (pin "2") (pinfunction "2_2") (pintype "passive"))
      (node (ref "D14") (pin "A") (pinfunction "A_A") (pintype "passive"))
      (node (ref "D15") (pin "C") (pinfunction "C_C") (pintype "passive"))
      (node (ref "H2") (pin "1") (pinfunction "P_1") (pintype "passive"))
      (node (ref "J2") (pin "A1") (pinfunction "1_A1") (pintype "passive"))
      (node (ref "J2") (pin "A2") (pinfunction "1_A2") (pintype "passive"))
      (node (ref "R27") (pin "1") (pinfunction "1_1") (pintype "passive"))
    )
    (net (code "25") (name "Net-(H10-P)") (class "Default")
      (node (ref "C2") (pin "1") (pinfunction "1_1") (pintype "passive"))
      (node (ref "C7") (pin "1") (pinfunction "1_1") (pintype "passive"))
      (node (ref "F1") (pin "1A") (pinfunction "1A_1A") (pintype "passive"))
      (node (ref "H10") (pin "1") (pinfunction "P_1") (pintype "passive"))
      (node (ref "J10") (pin "A1") (pinfunction "1_A1") (pintype "passive"))
      (node (ref "J10") (pin "A2") (pinfunction "1_A2") (pintype "passive"))
    )
    (net (code "26") (name "Net-(H11-P)") (class "Default")
      (node (ref "C7") (pin "2") (pinfunction "2_2") (pintype "passive"))
      (node (ref "D5") (pin "A") (pinfunction "A_A") (pintype "passive"))
      (node (ref "D6") (pin "C") (pinfunction "C_C") (pintype "passive"))
      (node (ref "H11") (pin "1") (pinfunction "P_1") (pintype "passive"))
      (node (ref "J11") (pin "A1") (pinfunction "1_A1") (pintype "passive"))
      (node (ref "J11") (pin "A2") (pinfunction "1_A2") (pintype "passive"))
      (node (ref "R23") (pin "1") (pinfunction "1_1") (pintype "passive"))
    )
    (net (code "27") (name "Net-(H12-P)") (class "Default")
      (node (ref "C18") (pin "1") (pinfunction "1_1") (pintype "passive"))
      (node (ref "C8") (pin "1") (pinfunction "1_1") (pintype "passive"))
      (node (ref "D11") (pin "C") (pinfunction "C_C") (pintype "passive"))
      (node (ref "D8") (pin "A") (pinfunction "A_A") (pintype "passive"))
      (node (ref "H12") (pin "1") (pinfunction "P_1") (pintype "passive"))
      (node (ref "J12") (pin "A1") (pinfunction "1_A1") (pintype "passive"))
      (node (ref "J12") (pin "A2") (pinfunction "1_A2") (pintype "passive"))
    )
    (net (code "28") (name "Net-(H13-P)") (class "Default")
      (node (ref "C8") (pin "2") (pinfunction "2_2") (pintype "passive"))
      (node (ref "F2") (pin "1A") (pinfunction "1A_1A") (pintype "passive"))
      (node (ref "H13") (pin "1") (pinfunction "P_1") (pintype "passive"))
      (node (ref "J13") (pin "A1") (pinfunction "1_A1") (pintype "passive"))
      (node (ref "J13") (pin "A2") (pinfunction "1_A2") (pintype "passive"))
      (node (ref "R24") (pin "1") (pinfunction "1_1") (pintype "passive"))
    )
    (net (code "29") (name "Net-(H30-P)") (class "Default")
      (node (ref "C19") (pin "1") (pinfunction "1_1") (pintype "passive"))
      (node (ref "C27") (pin "1") (pinfunction "1_1") (pintype "passive"))
      (node (ref "F4") (pin "1A") (pinfunction "1A_1A") (pintype "passive"))
      (node (ref "H30") (pin "1") (pinfunction "P_1") (pintype "passive"))
      (node (ref "J30") (pin "A1") (pinfunction "1_A1") (pintype "passive"))
      (node (ref "J30") (pin "A2") (pinfunction "1_A2") (pintype "passive"))
    )
    (net (code "30") (name "Net-(H31-P)") (class "Default")
      (node (ref "C27") (pin "2") (pinfunction "2_2") (pintype "passive"))
      (node (ref "D19") (pin "A") (pinfunction "A_A") (pintype "passive"))
      (node (ref "D20") (pin "C") (pinfunction "C_C") (pintype "passive"))
      (node (ref "H31") (pin "1") (pinfunction "P_1") (pintype "passive"))
      (node (ref "J31") (pin "A1") (pinfunction "1_A1") (pintype "passive"))
      (node (ref "J31") (pin "A2") (pinfunction "1_A2") (pintype "passive"))
      (node (ref "R25") (pin "1") (pinfunction "1_1") (pintype "passive"))
    )
    (net (code "31") (name "Net-(H32-P)") (class "Default")
      (node (ref "C20") (pin "1") (pinfunction "1_1") (pintype "passive"))
      (node (ref "C28") (pin "1") (pinfunction "1_1") (pintype "passive"))
      (node (ref "D22") (pin "A") (pinfunction "A_A") (pintype "passive"))
      (node (ref "D25") (pin "C") (pinfunction "C_C") (pintype "passive"))
      (node (ref "H32") (pin "1") (pinfunction "P_1") (pintype "passive"))
      (node (ref "J32") (pin "A1") (pinfunction "1_A1") (pintype "passive"))
      (node (ref "J32") (pin "A2") (pinfunction "1_A2") (pintype "passive"))
    )
    (net (code "32") (name "Net-(H33-P)") (class "Default")
      (node (ref "C28") (pin "2") (pinfunction "2_2") (pintype "passive"))
      (node (ref "F5") (pin "1A") (pinfunction "1A_1A") (pintype "passive"))
      (node (ref "H33") (pin "1") (pinfunction "P_1") (pintype "passive"))
      (node (ref "J33") (pin "A1") (pinfunction "1_A1") (pintype "passive"))
      (node (ref "J33") (pin "A2") (pinfunction "1_A2") (pintype "passive"))
      (node (ref "R26") (pin "1") (pinfunction "1_1") (pintype "passive"))
    )
    (net (code "33") (name "Net-(IC1-C.4-I{slash}O)") (class "Default")
      (node (ref "IC1") (pin "3") (pinfunction "C.4-I/O_3") (pintype "bidirectional"))
      (node (ref "R21") (pin "1") (pinfunction "1_1") (pintype "passive"))
      (node (ref "R22") (pin "2") (pinfunction "2_2") (pintype "passive"))
    )
    (net (code "34") (name "Net-(IC1-C.5-SERIN)") (class "Default")
      (node (ref "IC1") (pin "2") (pinfunction "C.5-SERIN_2") (pintype "input"))
      (node (ref "R2") (pin "1") (pinfunction "1_1") (pintype "passive"))
    )
    (net (code "35") (name "Net-(IC1-I{slash}O-C.1)") (class "Default")
      (node (ref "IC1") (pin "6") (pinfunction "I/O-C.1_6") (pintype "bidirectional"))
      (node (ref "PV2") (pin "1") (pinfunction "A_1") (pintype "passive"))
    )
    (net (code "36") (name "Net-(IC1-I{slash}O-C.2)") (class "Default")
      (node (ref "IC1") (pin "5") (pinfunction "I/O-C.2_5") (pintype "bidirectional"))
      (node (ref "R19") (pin "1") (pinfunction "1_1") (pintype "passive"))
      (node (ref "R20") (pin "2") (pinfunction "2_2") (pintype "passive"))
    )
    (net (code "37") (name "Net-(IC1-SEROUT-C.0)") (class "Default")
      (node (ref "IC1") (pin "7") (pinfunction "SEROUT-C.0_7") (pintype "output"))
      (node (ref "LED") (pin "A") (pinfunction "A_A") (pintype "passive"))
    )
    (net (code "38") (name "Net-(IC1-V+)") (class "Default")
      (node (ref "C1") (pin "2") (pinfunction "2_2") (pintype "passive"))
      (node (ref "C16") (pin "+") (pinfunction "+_+") (pintype "passive"))
      (node (ref "IC1") (pin "1") (pinfunction "V+_1") (pintype "power_in"))
      (node (ref "IC2") (pin "1") (pinfunction "VO_1") (pintype "passive"))
      (node (ref "R21") (pin "2") (pinfunction "2_2") (pintype "passive"))
      (node (ref "R4") (pin "1") (pinfunction "1_1") (pintype "passive"))
    )
    (net (code "39") (name "Net-(IC2-VI)") (class "Default")
      (node (ref "C17") (pin "+") (pinfunction "+_+") (pintype "passive"))
      (node (ref "C23") (pin "+") (pinfunction "+_+") (pintype "passive"))
      (node (ref "C25") (pin "+") (pinfunction "+_+") (pintype "passive"))
      (node (ref "D19") (pin "C") (pinfunction "C_C") (pintype "passive"))
      (node (ref "D21") (pin "C") (pinfunction "C_C") (pintype "passive"))
      (node (ref "IC2") (pin "3") (pinfunction "VI_3") (pintype "input"))
      (node (ref "Q6") (pin "C") (pinfunction "C_C") (pintype "passive"))
      (node (ref "R7") (pin "2") (pinfunction "2_2") (pintype "passive"))
      (node (ref "UNREG+") (pin "1") (pinfunction "P_1") (pintype "passive"))
    )
    (net (code "40") (name "Net-(IC3A--IN)") (class "Default")
      (node (ref "IC3") (pin "2") (pinfunction "-IN_2") (pintype "input"))
      (node (ref "R32") (pin "2") (pinfunction "2_2") (pintype "passive"))
      (node (ref "R34") (pin "1") (pinfunction "1_1") (pintype "passive"))
    )
    (net (code "41") (name "Net-(IC3A-OUT)") (class "Default")
      (node (ref "IC3") (pin "1") (pinfunction "OUT_1") (pintype "output"))
      (node (ref "R36") (pin "1") (pinfunction "1_1") (pintype "passive"))
    )
    (net (code "42") (name "Net-(IC3B--IN)") (class "Default")
      (node (ref "IC3") (pin "6") (pinfunction "-IN_6") (pintype "input"))
      (node (ref "R33") (pin "2") (pinfunction "2_2") (pintype "passive"))
      (node (ref "R35") (pin "1") (pinfunction "1_1") (pintype "passive"))
    )
    (net (code "43") (name "Net-(IC3B-OUT)") (class "Default")
      (node (ref "IC3") (pin "7") (pinfunction "OUT_7") (pintype "output"))
      (node (ref "R37") (pin "2") (pinfunction "2_2") (pintype "passive"))
    )
    (net (code "44") (name "Net-(IC3C-V+)") (class "Default")
      (node (ref "C29") (pin "+") (pinfunction "+_+") (pintype "passive"))
      (node (ref "C30") (pin "+") (pinfunction "+_+") (pintype "passive"))
      (node (ref "C43") (pin "+") (pinfunction "+_+") (pintype "passive"))
      (node (ref "IC3") (pin "8") (pinfunction "V+_8") (pintype "power_in"))
      (node (ref "R7") (pin "1") (pinfunction "1_1") (pintype "passive"))
      (node (ref "R8") (pin "2") (pinfunction "2_2") (pintype "passive"))
    )
    (net (code "45") (name "Net-(IC3C-V-)") (class "Default")
      (node (ref "C32") (pin "-") (pinfunction "-_-") (pintype "passive"))
      (node (ref "C33") (pin "-") (pinfunction "-_-") (pintype "passive"))
      (node (ref "C44") (pin "-") (pinfunction "-_-") (pintype "passive"))
      (node (ref "IC3") (pin "4") (pinfunction "V-_4") (pintype "power_in"))
      (node (ref "R28") (pin "2") (pinfunction "2_2") (pintype "passive"))
      (node (ref "R29") (pin "1") (pinfunction "1_1") (pintype "passive"))
    )
    (net (code "46") (name "Net-(IC4-ADJ)") (class "Default")
      (node (ref "IC4") (pin "1") (pinfunction "ADJ_1") (pintype "input"))
      (node (ref "Q8") (pin "G") (pinfunction "G_G") (pintype "passive"))
      (node (ref "R40") (pin "1") (pinfunction "1_1") (pintype "passive"))
      (node (ref "VR1") (pin "C") (pinfunction "C_C") (pintype "passive"))
    )
    (net (code "47") (name "Net-(IC4-IN)") (class "Default")
      (node (ref "C21") (pin "+") (pinfunction "+_+") (pintype "passive"))
      (node (ref "C22") (pin "+") (pinfunction "+_+") (pintype "passive"))
      (node (ref "C45") (pin "1") (pinfunction "1_1") (pintype "passive"))
      (node (ref "D1") (pin "C") (pinfunction "C_C") (pintype "passive"))
      (node (ref "D14") (pin "C") (pinfunction "C_C") (pintype "passive"))
      (node (ref "D16") (pin "C") (pinfunction "C_C") (pintype "passive"))
      (node (ref "IC4") (pin "3") (pinfunction "IN_3") (pintype "input"))
    )
    (net (code "48") (name "Net-(LED-C)") (class "Default")
      (node (ref "LED") (pin "K") (pinfunction "C_K") (pintype "passive"))
      (node (ref "R3") (pin "1") (pinfunction "1_1") (pintype "passive"))
    )
    (net (code "49") (name "Net-(LED1-PadA)") (class "Default")
      (node (ref "LED1") (pin "A") (pinfunction "A_A") (pintype "passive"))
      (node (ref "R43") (pin "1") (pinfunction "1_1") (pintype "passive"))
    )
    (net (code "50") (name "Net-(PV1-A)") (class "Default")
      (node (ref "PV1") (pin "1") (pinfunction "A_1") (pintype "passive"))
      (node (ref "PV2") (pin "2") (pinfunction "C_2") (pintype "passive"))
    )
    (net (code "51") (name "Net-(PV1-C)") (class "Default")
      (node (ref "PV1") (pin "2") (pinfunction "C_2") (pintype "passive"))
      (node (ref "R1") (pin "2") (pinfunction "2_2") (pintype "passive"))
    )
    (net (code "52") (name "Net-(PV1-EMIT)") (class "Default")
      (node (ref "PV1") (pin "3") (pinfunction "EMIT_3") (pintype "passive"))
      (node (ref "Q1") (pin "G") (pinfunction "G_G") (pintype "passive"))
      (node (ref "Q3") (pin "G") (pinfunction "G_G") (pintype "passive"))
    )
    (net (code "53") (name "Net-(PV2-COL)") (class "Default")
      (node (ref "C10") (pin "-") (pinfunction "-_-") (pintype "passive"))
      (node (ref "C12") (pin "2") (pinfunction "2_2") (pintype "passive"))
      (node (ref "C4") (pin "-") (pinfunction "-_-") (pintype "passive"))
      (node (ref "C6") (pin "-") (pinfunction "-_-") (pintype "passive"))
      (node (ref "D11") (pin "A") (pinfunction "A_A") (pintype "passive"))
      (node (ref "D9") (pin "A") (pinfunction "A_A") (pintype "passive"))
      (node (ref "PV2") (pin "4") (pinfunction "COL_4") (pintype "passive"))
      (node (ref "Q2") (pin "S") (pinfunction "S_S") (pintype "passive"))
      (node (ref "Q5") (pin "S") (pinfunction "S_S") (pintype "passive"))
      (node (ref "R11") (pin "2") (pinfunction "2_2") (pintype "passive"))
      (node (ref "R12") (pin "1") (pinfunction "1_1") (pintype "passive"))
      (node (ref "R13") (pin "2") (pinfunction "2_2") (pintype "passive"))
      (node (ref "R14") (pin "1") (pinfunction "1_1") (pintype "passive"))
      (node (ref "V-") (pin "1") (pinfunction "P_1") (pintype "passive"))
    )
    (net (code "54") (name "Net-(PV2-EMIT)") (class "Default")
      (node (ref "PV2") (pin "3") (pinfunction "EMIT_3") (pintype "passive"))
      (node (ref "Q2") (pin "G") (pinfunction "G_G") (pintype "passive"))
      (node (ref "Q5") (pin "G") (pinfunction "G_G") (pintype "passive"))
    )
    (net (code "55") (name "Net-(Q4-B)") (class "Default")
      (node (ref "Q4") (pin "2") (pinfunction "B_2") (pintype "passive"))
      (node (ref "R15") (pin "2") (pinfunction "2_2") (pintype "passive"))
    )
    (net (code "56") (name "Net-(Q4-C)") (class "Default")
      (node (ref "C15") (pin "1") (pinfunction "1_1") (pintype "passive"))
      (node (ref "Q4") (pin "3") (pinfunction "C_3") (pintype "passive"))
      (node (ref "R16") (pin "1") (pinfunction "1_1") (pintype "passive"))
    )
    (net (code "57") (name "Net-(Q6-PadB)") (class "Default")
      (node (ref "Q6") (pin "B") (pinfunction "B_B") (pintype "passive"))
      (node (ref "R36") (pin "2") (pinfunction "2_2") (pintype "passive"))
    )
    (net (code "58") (name "Net-(Q7-PadB)") (class "Default")
      (node (ref "Q7") (pin "B") (pinfunction "B_B") (pintype "passive"))
      (node (ref "R37") (pin "1") (pinfunction "1_1") (pintype "passive"))
    )
    (net (code "59") (name "Net-(Q8-PadS)") (class "Default")
      (node (ref "Q8") (pin "S") (pinfunction "S_S") (pintype "passive"))
      (node (ref "R40") (pin "2") (pinfunction "2_2") (pintype "passive"))
    )
    (net (code "60") (name "Net-(R41-Pad1)") (class "Default")
      (node (ref "R41") (pin "1") (pinfunction "1_1") (pintype "passive"))
      (node (ref "R42") (pin "2") (pinfunction "2_2") (pintype "passive"))
      (node (ref "VR1") (pin "R") (pinfunction "R_R") (pintype "passive"))
    )
    (net (code "61") (name "Net-(UNREG--P)") (class "Default")
      (node (ref "C24") (pin "-") (pinfunction "-_-") (pintype "passive"))
      (node (ref "C26") (pin "-") (pinfunction "-_-") (pintype "passive"))
      (node (ref "D23") (pin "A") (pinfunction "A_A") (pintype "passive"))
      (node (ref "D25") (pin "A") (pinfunction "A_A") (pintype "passive"))
      (node (ref "Q7") (pin "C") (pinfunction "C_C") (pintype "passive"))
      (node (ref "R28") (pin "1") (pinfunction "1_1") (pintype "passive"))
      (node (ref "UNREG-") (pin "1") (pinfunction "P_1") (pintype "passive"))
    )
    (net (code "62") (name "Net-(V+-P)") (class "Default")
      (node (ref "C11") (pin "1") (pinfunction "1_1") (pintype "passive"))
      (node (ref "C3") (pin "+") (pinfunction "+_+") (pintype "passive"))
      (node (ref "C5") (pin "+") (pinfunction "+_+") (pintype "passive"))
      (node (ref "C9") (pin "+") (pinfunction "+_+") (pintype "passive"))
      (node (ref "D5") (pin "C") (pinfunction "C_C") (pintype "passive"))
      (node (ref "D7") (pin "C") (pinfunction "C_C") (pintype "passive"))
      (node (ref "Q1") (pin "D") (pinfunction "D_D") (pintype "passive"))
      (node (ref "Q3") (pin "D") (pinfunction "D_D") (pintype "passive"))
      (node (ref "R10") (pin "1") (pinfunction "1_1") (pintype "passive"))
      (node (ref "R5") (pin "2") (pinfunction "2_2") (pintype "passive"))
      (node (ref "R6") (pin "1") (pinfunction "1_1") (pintype "passive"))
      (node (ref "R9") (pin "2") (pinfunction "2_2") (pintype "passive"))
      (node (ref "V+") (pin "1") (pinfunction "P_1") (pintype "passive"))
    )
    (net (code "63") (name "VCC") (class "Default")
      (node (ref "H4") (pin "1") (pinfunction "P_1") (pintype "passive"))
      (node (ref "J4") (pin "A1") (pinfunction "1_A1") (pintype "passive"))
      (node (ref "J4") (pin "A2") (pinfunction "1_A2") (pintype "passive"))
      (node (ref "PV1") (pin "4") (pinfunction "COL_4") (pintype "passive"))
      (node (ref "Q1") (pin "S") (pinfunction "S_S") (pintype "passive"))
      (node (ref "Q3") (pin "S") (pinfunction "S_S") (pintype "passive"))
      (node (ref "R19") (pin "2") (pinfunction "2_2") (pintype "passive"))
    )
    (net (code "64") (name "VDR") (class "Default")
      (node (ref "C46") (pin "+") (pinfunction "+_+") (pintype "passive"))
      (node (ref "D1") (pin "A") (pinfunction "A_A") (pintype "passive"))
      (node (ref "H3") (pin "1") (pinfunction "P_1") (pintype "passive"))
      (node (ref "IC4") (pin "2") (pinfunction "OUT_2") (pintype "passive"))
      (node (ref "J3") (pin "A1") (pinfunction "1_A1") (pintype "passive"))
      (node (ref "J3") (pin "A2") (pinfunction "1_A2") (pintype "passive"))
      (node (ref "Q8") (pin "D") (pinfunction "D_D") (pintype "passive"))
      (node (ref "R41") (pin "2") (pinfunction "2_2") (pintype "passive"))
      (node (ref "R43") (pin "2") (pinfunction "2_2") (pintype "passive"))
    )
    (net (code "65") (name "VEE") (class "Default")
      (node (ref "C21") (pin "-") (pinfunction "-_-") (pintype "passive"))
      (node (ref "C22") (pin "-") (pinfunction "-_-") (pintype "passive"))
      (node (ref "C45") (pin "2") (pinfunction "2_2") (pintype "passive"))
      (node (ref "C46") (pin "-") (pinfunction "-_-") (pintype "passive"))
      (node (ref "D15") (pin "A") (pinfunction "A_A") (pintype "passive"))
      (node (ref "D3") (pin "A") (pinfunction "A_A") (pintype "passive"))
      (node (ref "H5") (pin "1") (pinfunction "P_1") (pintype "passive"))
      (node (ref "J5") (pin "A1") (pinfunction "1_A1") (pintype "passive"))
      (node (ref "J5") (pin "A2") (pinfunction "1_A2") (pintype "passive"))
      (node (ref "LED1") (pin "K") (pinfunction "C_K") (pintype "passive"))
      (node (ref "Q2") (pin "D") (pinfunction "D_D") (pintype "passive"))
      (node (ref "Q5") (pin "D") (pinfunction "D_D") (pintype "passive"))
      (node (ref "R22") (pin "1") (pinfunction "1_1") (pintype "passive"))
      (node (ref "R42") (pin "1") (pinfunction "1_1") (pintype "passive"))
      (node (ref "VR1") (pin "A") (pinfunction "A_A") (pintype "passive"))
    )
    (net (code "66") (name "unconnected-(F1-Pad1B)") (class "Default")
      (node (ref "F1") (pin "1B") (pinfunction "1B_1B") (pintype "passive"))
    )
    (net (code "67") (name "unconnected-(F1-Pad2B)") (class "Default")
      (node (ref "F1") (pin "2B") (pinfunction "2B_2B") (pintype "passive"))
    )
    (net (code "68") (name "unconnected-(F2-Pad1B)") (class "Default")
      (node (ref "F2") (pin "1B") (pinfunction "1B_1B") (pintype "passive"))
    )
    (net (code "69") (name "unconnected-(F2-Pad2B)") (class "Default")
      (node (ref "F2") (pin "2B") (pinfunction "2B_2B") (pintype "passive"))
    )
    (net (code "70") (name "unconnected-(F3-Pad1B)") (class "Default")
      (node (ref "F3") (pin "1B") (pinfunction "1B_1B") (pintype "passive"))
    )
    (net (code "71") (name "unconnected-(F3-Pad2B)") (class "Default")
      (node (ref "F3") (pin "2B") (pinfunction "2B_2B") (pintype "passive"))
    )
    (net (code "72") (name "unconnected-(F4-Pad1B)") (class "Default")
      (node (ref "F4") (pin "1B") (pinfunction "1B_1B") (pintype "passive"))
    )
    (net (code "73") (name "unconnected-(F4-Pad2B)") (class "Default")
      (node (ref "F4") (pin "2B") (pinfunction "2B_2B") (pintype "passive"))
    )
    (net (code "74") (name "unconnected-(F5-Pad1B)") (class "Default")
      (node (ref "F5") (pin "1B") (pinfunction "1B_1B") (pintype "passive"))
    )
    (net (code "75") (name "unconnected-(F5-Pad2B)") (class "Default")
      (node (ref "F5") (pin "2B") (pinfunction "2B_2B") (pintype "passive"))
    )
  )
)
